# 130731_AriloRX_0_1.net
KiCad netlist of a schematic drawn in EAGLE
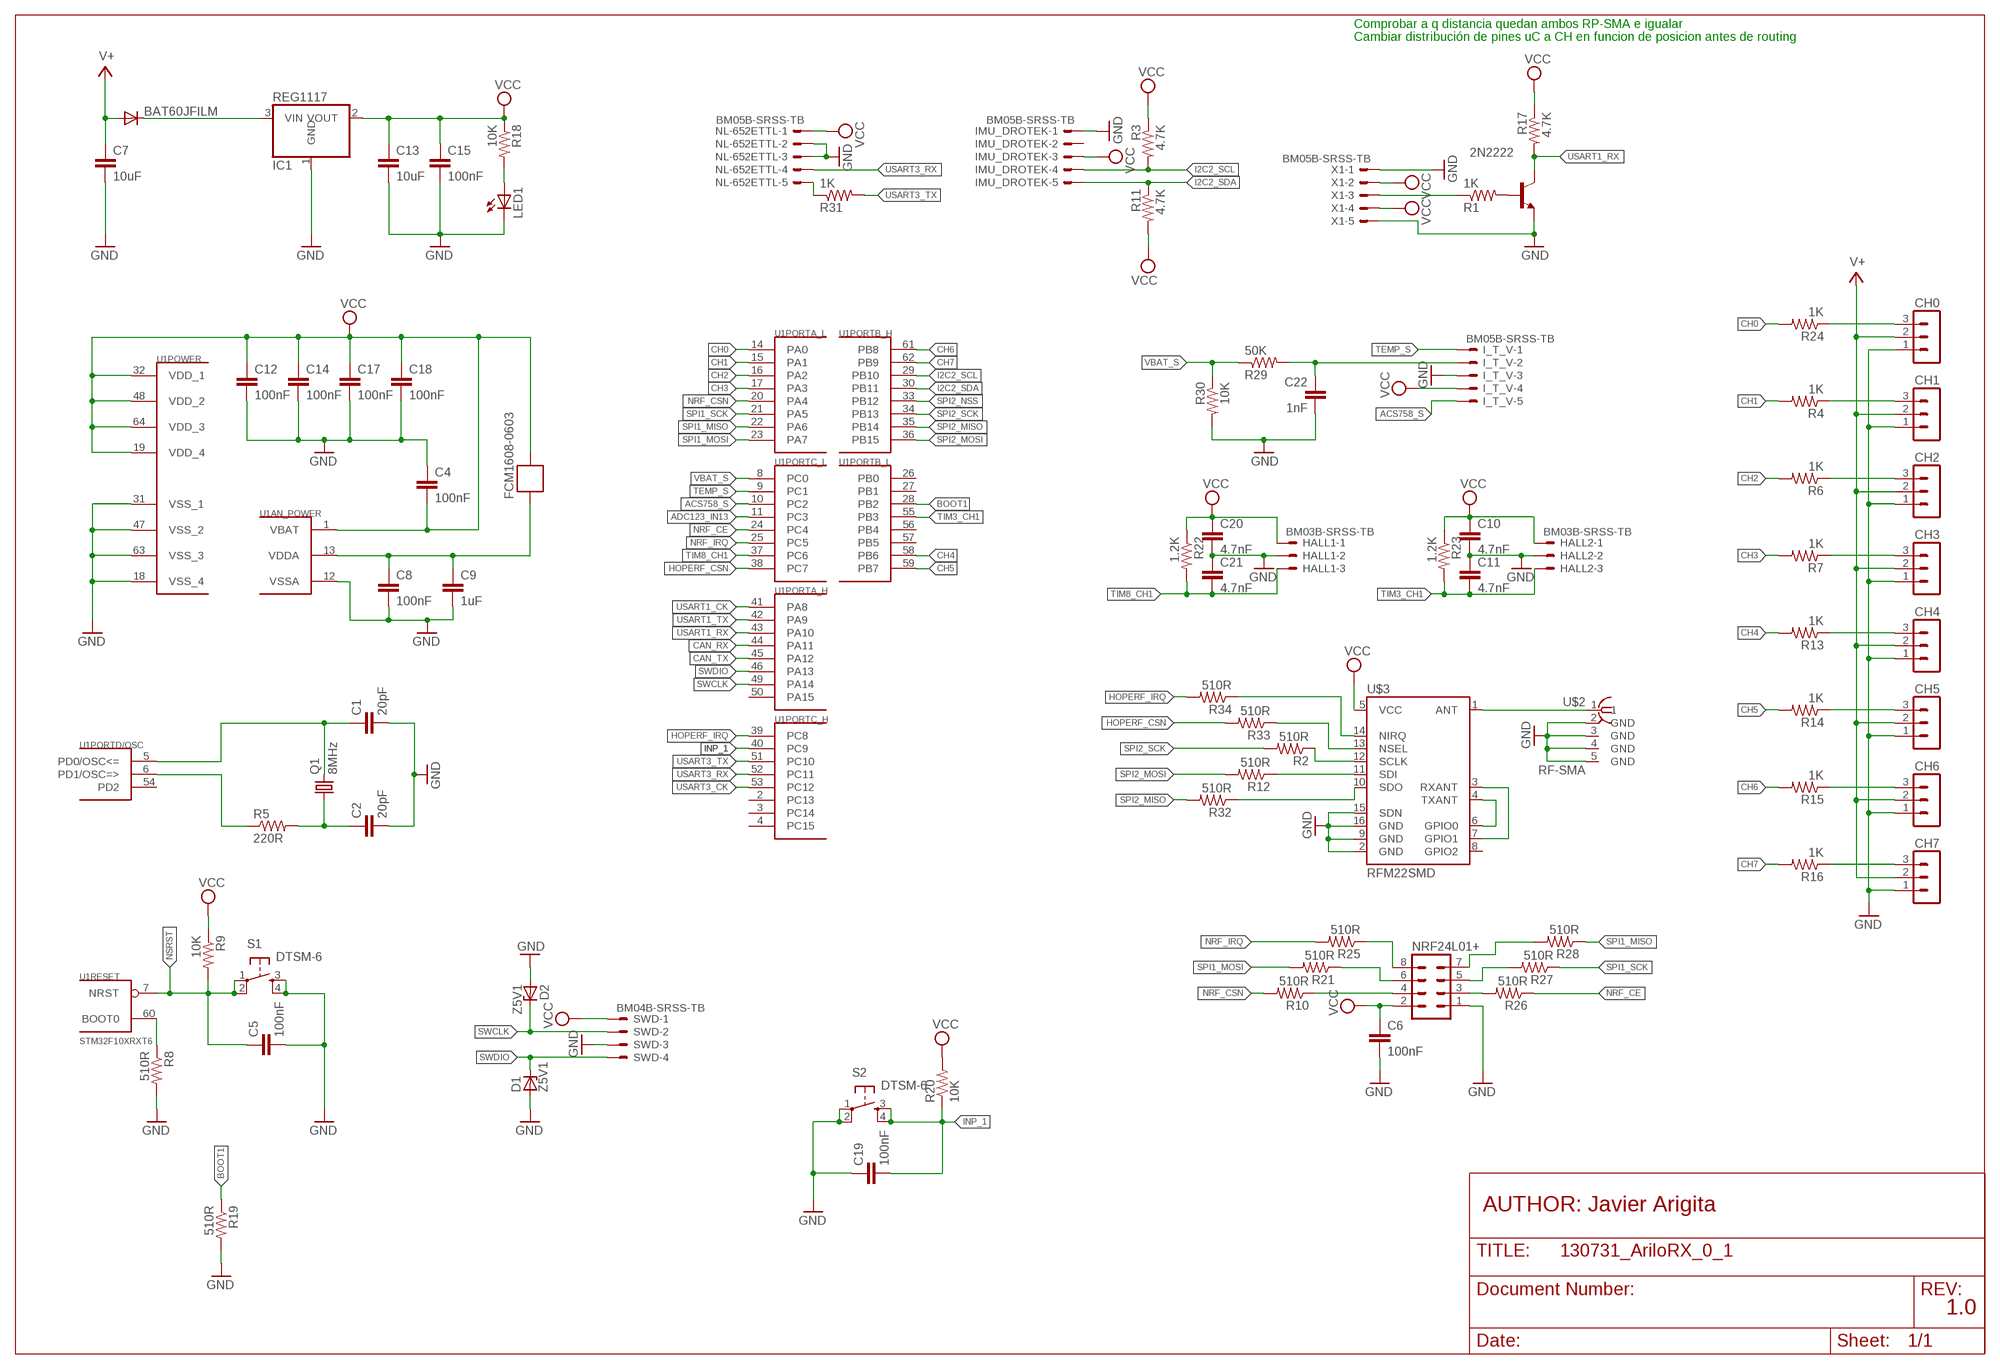
[diagram p0: schematic, sheet 1]

(export (version "E")
  (design (tool "Eeschema 10.0.6"))
  (components
    (comp (ref "2N2222")
      (value "MMBT2222ALT1-NPN-SOT23-BEC")
      (footprint "eagle-import:SOT23-BEC")
      (libsource (lib "eagle-import") (part "-NPN-SOT23-BECMMBT2222ALT1"))
    )
    (comp (ref "BAT60JFILM")
      (value "DIODE-SOD323-R")
      (footprint "eagle-import:SOD323-R")
      (libsource (lib "eagle-import") (part "DIODE-SOD323-R"))
    )
    (comp (ref "C1")
      (value "20pF")
      (footprint "eagle-import:C0805")
      (libsource (lib "eagle-import") (part "C-EUC0805"))
    )
    (comp (ref "C2")
      (value "20pF")
      (footprint "eagle-import:C0805")
      (libsource (lib "eagle-import") (part "C-EUC0805"))
    )
    (comp (ref "C4")
      (value "100nF")
      (footprint "eagle-import:C0805")
      (libsource (lib "eagle-import") (part "C-EUC0805"))
    )
    (comp (ref "C5")
      (value "100nF")
      (footprint "eagle-import:C0805")
      (libsource (lib "eagle-import") (part "C-EUC0805"))
    )
    (comp (ref "C6")
      (value "100nF")
      (footprint "eagle-import:C0805")
      (libsource (lib "eagle-import") (part "C-EUC0805"))
    )
    (comp (ref "C7")
      (value "10uF")
      (footprint "eagle-import:C3216")
      (libsource (lib "eagle-import") (part "resistor_C-EUC3216"))
    )
    (comp (ref "C8")
      (value "100nF")
      (footprint "eagle-import:C0805")
      (libsource (lib "eagle-import") (part "C-EUC0805"))
    )
    (comp (ref "C9")
      (value "1uF")
      (footprint "eagle-import:C3216")
      (libsource (lib "eagle-import") (part "resistor_C-EUC3216"))
    )
    (comp (ref "C10")
      (value "4.7nF")
      (footprint "eagle-import:C0805")
      (libsource (lib "eagle-import") (part "C-EUC0805"))
    )
    (comp (ref "C11")
      (value "4.7nF")
      (footprint "eagle-import:C0805")
      (libsource (lib "eagle-import") (part "C-EUC0805"))
    )
    (comp (ref "C12")
      (value "100nF")
      (footprint "eagle-import:C0805")
      (libsource (lib "eagle-import") (part "C-EUC0805"))
    )
    (comp (ref "C13")
      (value "10uF")
      (footprint "eagle-import:C3216")
      (libsource (lib "eagle-import") (part "resistor_C-EUC3216"))
    )
    (comp (ref "C14")
      (value "100nF")
      (footprint "eagle-import:C0805")
      (libsource (lib "eagle-import") (part "C-EUC0805"))
    )
    (comp (ref "C15")
      (value "100nF")
      (footprint "eagle-import:C0805")
      (libsource (lib "eagle-import") (part "C-EUC0805"))
    )
    (comp (ref "C17")
      (value "100nF")
      (footprint "eagle-import:C0805")
      (libsource (lib "eagle-import") (part "C-EUC0805"))
    )
    (comp (ref "C18")
      (value "100nF")
      (footprint "eagle-import:C0805")
      (libsource (lib "eagle-import") (part "C-EUC0805"))
    )
    (comp (ref "C19")
      (value "100nF")
      (footprint "eagle-import:C0805")
      (libsource (lib "eagle-import") (part "C-EUC0805"))
    )
    (comp (ref "C20")
      (value "4.7nF")
      (footprint "eagle-import:C0805")
      (libsource (lib "eagle-import") (part "C-EUC0805"))
    )
    (comp (ref "C21")
      (value "4.7nF")
      (footprint "eagle-import:C0805")
      (libsource (lib "eagle-import") (part "C-EUC0805"))
    )
    (comp (ref "C22")
      (value "1nF")
      (footprint "eagle-import:C0805")
      (libsource (lib "eagle-import") (part "C-EUC0805"))
    )
    (comp (ref "CH0")
      (value "MA03-1")
      (footprint "eagle-import:MA03-1")
      (libsource (lib "eagle-import") (part "MA03-1"))
    )
    (comp (ref "CH1")
      (value "MA03-1")
      (footprint "eagle-import:MA03-1")
      (libsource (lib "eagle-import") (part "MA03-1"))
    )
    (comp (ref "CH2")
      (value "MA03-1")
      (footprint "eagle-import:MA03-1")
      (libsource (lib "eagle-import") (part "MA03-1"))
    )
    (comp (ref "CH3")
      (value "MA03-1")
      (footprint "eagle-import:MA03-1")
      (libsource (lib "eagle-import") (part "MA03-1"))
    )
    (comp (ref "CH4")
      (value "MA03-1")
      (footprint "eagle-import:MA03-1")
      (libsource (lib "eagle-import") (part "MA03-1"))
    )
    (comp (ref "CH5")
      (value "MA03-1")
      (footprint "eagle-import:MA03-1")
      (libsource (lib "eagle-import") (part "MA03-1"))
    )
    (comp (ref "CH6")
      (value "MA03-1")
      (footprint "eagle-import:MA03-1")
      (libsource (lib "eagle-import") (part "MA03-1"))
    )
    (comp (ref "CH7")
      (value "MA03-1")
      (footprint "eagle-import:MA03-1")
      (libsource (lib "eagle-import") (part "MA03-1"))
    )
    (comp (ref "D1")
      (value "Z5V1")
      (footprint "eagle-import:SOD80C")
      (libsource (lib "eagle-import") (part "ZENER-DIODESOD80C"))
    )
    (comp (ref "D2")
      (value "Z5V1")
      (footprint "eagle-import:SOD80C")
      (libsource (lib "eagle-import") (part "ZENER-DIODESOD80C"))
    )
    (comp (ref "FCM1608-0603")
      (value "FERRITE-BEAD")
      (footprint "eagle-import:R0603")
      (libsource (lib "eagle-import") (part "FERRITE-BEAD"))
    )
    (comp (ref "HALL1")
      (value "BM03B-SRSS-TB")
      (footprint "eagle-import:BM03B-SRSS-TB")
      (libsource (lib "eagle-import") (part "?M03B-SRSS-TBB"))
    )
    (comp (ref "HALL2")
      (value "BM03B-SRSS-TB")
      (footprint "eagle-import:BM03B-SRSS-TB")
      (libsource (lib "eagle-import") (part "?M03B-SRSS-TBB"))
    )
    (comp (ref "IC1")
      (value "REG1117")
      (footprint "eagle-import:SOT223")
      (libsource (lib "eagle-import") (part "REG1117"))
    )
    (comp (ref "IMU_DROTEK")
      (value "BM05B-SRSS-TB")
      (footprint "eagle-import:BM05B-SRSS-TB")
      (libsource (lib "eagle-import") (part "?M05B-SRSS-TBB"))
    )
    (comp (ref "I_T_V")
      (value "BM05B-SRSS-TB")
      (footprint "eagle-import:BM05B-SRSS-TB")
      (libsource (lib "eagle-import") (part "?M05B-SRSS-TBB"))
    )
    (comp (ref "LED1")
      (value "LED0805")
      (footprint "eagle-import:CHIPLED_0805")
      (libsource (lib "eagle-import") (part "LED0805"))
    )
    (comp (ref "NL-652ETTL")
      (value "BM05B-SRSS-TB")
      (footprint "eagle-import:BM05B-SRSS-TB")
      (libsource (lib "eagle-import") (part "?M05B-SRSS-TBB"))
    )
    (comp (ref "NRF24L01+")
      (value "MA04-2")
      (footprint "eagle-import:MA04-2")
      (libsource (lib "eagle-import") (part "MA04-2"))
    )
    (comp (ref "Q1")
      (value "8MHz")
      (footprint "eagle-import:SM49")
      (libsource (lib "eagle-import") (part "CRYSTALSM49"))
    )
    (comp (ref "R1")
      (value "1K")
      (footprint "eagle-import:R0805")
      (libsource (lib "eagle-import") (part "RESISTOR0805"))
    )
    (comp (ref "R2")
      (value "510R")
      (footprint "eagle-import:R0805")
      (libsource (lib "eagle-import") (part "RESISTOR0805"))
    )
    (comp (ref "R3")
      (value "4.7K")
      (footprint "eagle-import:R0805")
      (libsource (lib "eagle-import") (part "RESISTOR0805"))
    )
    (comp (ref "R4")
      (value "1K")
      (footprint "eagle-import:R0805")
      (libsource (lib "eagle-import") (part "RESISTOR0805"))
    )
    (comp (ref "R5")
      (value "220R")
      (footprint "eagle-import:R0805")
      (libsource (lib "eagle-import") (part "RESISTOR0805"))
    )
    (comp (ref "R6")
      (value "1K")
      (footprint "eagle-import:R0805")
      (libsource (lib "eagle-import") (part "RESISTOR0805"))
    )
    (comp (ref "R7")
      (value "1K")
      (footprint "eagle-import:R0805")
      (libsource (lib "eagle-import") (part "RESISTOR0805"))
    )
    (comp (ref "R8")
      (value "510R")
      (footprint "eagle-import:R0805")
      (libsource (lib "eagle-import") (part "RESISTOR0805"))
    )
    (comp (ref "R9")
      (value "10K")
      (footprint "eagle-import:R0805")
      (libsource (lib "eagle-import") (part "RESISTOR0805"))
    )
    (comp (ref "R10")
      (value "510R")
      (footprint "eagle-import:R0805")
      (libsource (lib "eagle-import") (part "RESISTOR0805"))
    )
    (comp (ref "R11")
      (value "4.7K")
      (footprint "eagle-import:R0805")
      (libsource (lib "eagle-import") (part "RESISTOR0805"))
    )
    (comp (ref "R12")
      (value "510R")
      (footprint "eagle-import:R0805")
      (libsource (lib "eagle-import") (part "RESISTOR0805"))
    )
    (comp (ref "R13")
      (value "1K")
      (footprint "eagle-import:R0805")
      (libsource (lib "eagle-import") (part "RESISTOR0805"))
    )
    (comp (ref "R14")
      (value "1K")
      (footprint "eagle-import:R0805")
      (libsource (lib "eagle-import") (part "RESISTOR0805"))
    )
    (comp (ref "R15")
      (value "1K")
      (footprint "eagle-import:R0805")
      (libsource (lib "eagle-import") (part "RESISTOR0805"))
    )
    (comp (ref "R16")
      (value "1K")
      (footprint "eagle-import:R0805")
      (libsource (lib "eagle-import") (part "RESISTOR0805"))
    )
    (comp (ref "R17")
      (value "4.7K")
      (footprint "eagle-import:R0805")
      (libsource (lib "eagle-import") (part "RESISTOR0805"))
    )
    (comp (ref "R18")
      (value "10K")
      (footprint "eagle-import:R0805")
      (libsource (lib "eagle-import") (part "RESISTOR0805"))
    )
    (comp (ref "R19")
      (value "510R")
      (footprint "eagle-import:R0805")
      (libsource (lib "eagle-import") (part "RESISTOR0805"))
    )
    (comp (ref "R20")
      (value "10K")
      (footprint "eagle-import:R0805")
      (libsource (lib "eagle-import") (part "RESISTOR0805"))
    )
    (comp (ref "R21")
      (value "510R")
      (footprint "eagle-import:R0805")
      (libsource (lib "eagle-import") (part "RESISTOR0805"))
    )
    (comp (ref "R22")
      (value "1.2K")
      (footprint "eagle-import:R0805")
      (libsource (lib "eagle-import") (part "RESISTOR0805"))
    )
    (comp (ref "R23")
      (value "1.2K")
      (footprint "eagle-import:R0805")
      (libsource (lib "eagle-import") (part "RESISTOR0805"))
    )
    (comp (ref "R24")
      (value "1K")
      (footprint "eagle-import:R0805")
      (libsource (lib "eagle-import") (part "RESISTOR0805"))
    )
    (comp (ref "R25")
      (value "510R")
      (footprint "eagle-import:R0805")
      (libsource (lib "eagle-import") (part "RESISTOR0805"))
    )
    (comp (ref "R26")
      (value "510R")
      (footprint "eagle-import:R0805")
      (libsource (lib "eagle-import") (part "RESISTOR0805"))
    )
    (comp (ref "R27")
      (value "510R")
      (footprint "eagle-import:R0805")
      (libsource (lib "eagle-import") (part "RESISTOR0805"))
    )
    (comp (ref "R28")
      (value "510R")
      (footprint "eagle-import:R0805")
      (libsource (lib "eagle-import") (part "RESISTOR0805"))
    )
    (comp (ref "R29")
      (value "50K")
      (footprint "eagle-import:R0805")
      (libsource (lib "eagle-import") (part "RESISTOR0805"))
    )
    (comp (ref "R30")
      (value "10K")
      (footprint "eagle-import:R0805")
      (libsource (lib "eagle-import") (part "RESISTOR0805"))
    )
    (comp (ref "R31")
      (value "1K")
      (footprint "eagle-import:R0805")
      (libsource (lib "eagle-import") (part "RESISTOR0805"))
    )
    (comp (ref "R32")
      (value "510R")
      (footprint "eagle-import:R0805")
      (libsource (lib "eagle-import") (part "RESISTOR0805"))
    )
    (comp (ref "R33")
      (value "510R")
      (footprint "eagle-import:R0805")
      (libsource (lib "eagle-import") (part "RESISTOR0805"))
    )
    (comp (ref "R34")
      (value "510R")
      (footprint "eagle-import:R0805")
      (libsource (lib "eagle-import") (part "RESISTOR0805"))
    )
    (comp (ref "S1")
      (value "DTSM-6")
      (footprint "eagle-import:DTSM-6")
      (libsource (lib "eagle-import") (part "DTSM-6"))
    )
    (comp (ref "S2")
      (value "DTSM-6")
      (footprint "eagle-import:DTSM-6")
      (libsource (lib "eagle-import") (part "DTSM-6"))
    )
    (comp (ref "SWD")
      (value "BM04B-SRSS-TB")
      (footprint "eagle-import:BM04B-SRSS-TB")
      (libsource (lib "eagle-import") (part "?M04B-SRSS-TBB"))
    )
    (comp (ref "U$2")
      (value "RF-SMA")
      (footprint "eagle-import:BU-SMA-H")
      (libsource (lib "eagle-import") (part "RF-SMA"))
    )
    (comp (ref "U$3")
      (value "RFM22SMD")
      (footprint "eagle-import:RFM22-XXX-S2")
      (libsource (lib "eagle-import") (part "RFM22SMD"))
    )
    (comp (ref "U1")
      (value "STM32F10XRXT6")
      (footprint "eagle-import:TQFP64")
      (libsource (lib "eagle-import") (part "STM32F10XRXT6"))
    )
    (comp (ref "X1")
      (value "BM05B-SRSS-TB")
      (footprint "eagle-import:BM05B-SRSS-TB")
      (libsource (lib "eagle-import") (part "?M05B-SRSS-TBB"))
    )
  )
  (nets
    (net (code "1") (name "ACS758_S") (class "Default")
      (node (ref "I_T_V") (pin "5") (pinfunction "S_5") (pintype "passive"))
      (node (ref "U1") (pin "10") (pinfunction "PC2_10") (pintype "bidirectional"))
    )
    (net (code "2") (name "ADC123_IN13") (class "Default")
      (node (ref "U1") (pin "11") (pinfunction "PC3_11") (pintype "bidirectional"))
    )
    (net (code "3") (name "BOOT1") (class "Default")
      (node (ref "R19") (pin "1") (pinfunction "1_1") (pintype "passive"))
      (node (ref "U1") (pin "28") (pinfunction "PB2_28") (pintype "bidirectional"))
    )
    (net (code "4") (name "CAN_RX") (class "Default")
      (node (ref "U1") (pin "44") (pinfunction "PA11_44") (pintype "bidirectional"))
    )
    (net (code "5") (name "CAN_TX") (class "Default")
      (node (ref "U1") (pin "45") (pinfunction "PA12_45") (pintype "bidirectional"))
    )
    (net (code "6") (name "CH0") (class "Default")
      (node (ref "R24") (pin "2") (pinfunction "2_2") (pintype "passive"))
      (node (ref "U1") (pin "14") (pinfunction "PA0_14") (pintype "bidirectional"))
    )
    (net (code "7") (name "CH1") (class "Default")
      (node (ref "R4") (pin "2") (pinfunction "2_2") (pintype "passive"))
      (node (ref "U1") (pin "15") (pinfunction "PA1_15") (pintype "bidirectional"))
    )
    (net (code "8") (name "CH2") (class "Default")
      (node (ref "R6") (pin "2") (pinfunction "2_2") (pintype "passive"))
      (node (ref "U1") (pin "16") (pinfunction "PA2_16") (pintype "bidirectional"))
    )
    (net (code "9") (name "CH3") (class "Default")
      (node (ref "R7") (pin "2") (pinfunction "2_2") (pintype "passive"))
      (node (ref "U1") (pin "17") (pinfunction "PA3_17") (pintype "bidirectional"))
    )
    (net (code "10") (name "CH4") (class "Default")
      (node (ref "R13") (pin "2") (pinfunction "2_2") (pintype "passive"))
      (node (ref "U1") (pin "58") (pinfunction "PB6_58") (pintype "bidirectional"))
    )
    (net (code "11") (name "CH5") (class "Default")
      (node (ref "R14") (pin "2") (pinfunction "2_2") (pintype "passive"))
      (node (ref "U1") (pin "59") (pinfunction "PB7_59") (pintype "bidirectional"))
    )
    (net (code "12") (name "CH6") (class "Default")
      (node (ref "R15") (pin "2") (pinfunction "2_2") (pintype "passive"))
      (node (ref "U1") (pin "61") (pinfunction "PB8_61") (pintype "bidirectional"))
    )
    (net (code "13") (name "CH7") (class "Default")
      (node (ref "R16") (pin "2") (pinfunction "2_2") (pintype "passive"))
      (node (ref "U1") (pin "62") (pinfunction "PB9_62") (pintype "bidirectional"))
    )
    (net (code "14") (name "GND") (class "Default")
      (node (ref "2N2222") (pin "E") (pinfunction "E_E") (pintype "passive"))
      (node (ref "C1") (pin "2") (pinfunction "2_2") (pintype "passive"))
      (node (ref "C10") (pin "2") (pinfunction "2_2") (pintype "passive"))
      (node (ref "C11") (pin "1") (pinfunction "1_1") (pintype "passive"))
      (node (ref "C12") (pin "2") (pinfunction "2_2") (pintype "passive"))
      (node (ref "C13") (pin "2") (pinfunction "2_2") (pintype "passive"))
      (node (ref "C14") (pin "2") (pinfunction "2_2") (pintype "passive"))
      (node (ref "C15") (pin "2") (pinfunction "2_2") (pintype "passive"))
      (node (ref "C17") (pin "2") (pinfunction "2_2") (pintype "passive"))
      (node (ref "C18") (pin "2") (pinfunction "2_2") (pintype "passive"))
      (node (ref "C19") (pin "1") (pinfunction "1_1") (pintype "passive"))
      (node (ref "C2") (pin "2") (pinfunction "2_2") (pintype "passive"))
      (node (ref "C20") (pin "2") (pinfunction "2_2") (pintype "passive"))
      (node (ref "C21") (pin "1") (pinfunction "1_1") (pintype "passive"))
      (node (ref "C22") (pin "2") (pinfunction "2_2") (pintype "passive"))
      (node (ref "C4") (pin "1") (pinfunction "1_1") (pintype "passive"))
      (node (ref "C5") (pin "2") (pinfunction "2_2") (pintype "passive"))
      (node (ref "C6") (pin "2") (pinfunction "2_2") (pintype "passive"))
      (node (ref "C7") (pin "2") (pinfunction "2_2") (pintype "passive"))
      (node (ref "C8") (pin "2") (pinfunction "2_2") (pintype "passive"))
      (node (ref "C9") (pin "2") (pinfunction "2_2") (pintype "passive"))
      (node (ref "CH0") (pin "1") (pinfunction "1_1") (pintype "passive"))
      (node (ref "CH1") (pin "1") (pinfunction "1_1") (pintype "passive"))
      (node (ref "CH2") (pin "1") (pinfunction "1_1") (pintype "passive"))
      (node (ref "CH3") (pin "1") (pinfunction "1_1") (pintype "passive"))
      (node (ref "CH4") (pin "1") (pinfunction "1_1") (pintype "passive"))
      (node (ref "CH5") (pin "1") (pinfunction "1_1") (pintype "passive"))
      (node (ref "CH6") (pin "1") (pinfunction "1_1") (pintype "passive"))
      (node (ref "CH7") (pin "1") (pinfunction "1_1") (pintype "passive"))
      (node (ref "D1") (pin "A") (pinfunction "A_A") (pintype "passive"))
      (node (ref "D2") (pin "A") (pinfunction "A_A") (pintype "passive"))
      (node (ref "HALL1") (pin "2") (pinfunction "S_2") (pintype "passive"))
      (node (ref "HALL2") (pin "2") (pinfunction "S_2") (pintype "passive"))
      (node (ref "IC1") (pin "1") (pinfunction "GND_1") (pintype "power_in"))
      (node (ref "IMU_DROTEK") (pin "1") (pinfunction "S_1") (pintype "passive"))
      (node (ref "I_T_V") (pin "3") (pinfunction "S_3") (pintype "passive"))
      (node (ref "LED1") (pin "C") (pinfunction "C_C") (pintype "passive"))
      (node (ref "NL-652ETTL") (pin "2") (pinfunction "S_2") (pintype "passive"))
      (node (ref "NL-652ETTL") (pin "3") (pinfunction "S_3") (pintype "passive"))
      (node (ref "NRF24L01+") (pin "1") (pinfunction "1_1") (pintype "passive"))
      (node (ref "R19") (pin "2") (pinfunction "2_2") (pintype "passive"))
      (node (ref "R30") (pin "2") (pinfunction "2_2") (pintype "passive"))
      (node (ref "R8") (pin "2") (pinfunction "2_2") (pintype "passive"))
      (node (ref "S1") (pin "3") (pinfunction "3_3") (pintype "passive"))
      (node (ref "S1") (pin "4") (pinfunction "4_4") (pintype "passive"))
      (node (ref "S2") (pin "1") (pinfunction "1_1") (pintype "passive"))
      (node (ref "S2") (pin "2") (pinfunction "2_2") (pintype "passive"))
      (node (ref "SWD") (pin "3") (pinfunction "S_3") (pintype "passive"))
      (node (ref "U$2") (pin "2") (pinfunction "GND_2") (pintype "power_in"))
      (node (ref "U$2") (pin "3") (pinfunction "GND_3") (pintype "bidirectional"))
      (node (ref "U$2") (pin "4") (pinfunction "GND_4") (pintype "bidirectional"))
      (node (ref "U$2") (pin "5") (pinfunction "GND_5") (pintype "bidirectional"))
      (node (ref "U$3") (pin "15") (pinfunction "SDN_15") (pintype "input"))
      (node (ref "U$3") (pin "16") (pinfunction "GND_16") (pintype "power_in"))
      (node (ref "U$3") (pin "2") (pinfunction "GND_2") (pintype "power_in"))
      (node (ref "U$3") (pin "9") (pinfunction "GND_9") (pintype "power_in"))
      (node (ref "U1") (pin "12") (pinfunction "VSSA_12") (pintype "power_in"))
      (node (ref "U1") (pin "18") (pinfunction "VSS_4_18") (pintype "power_in"))
      (node (ref "U1") (pin "31") (pinfunction "VSS_1_31") (pintype "power_in"))
      (node (ref "U1") (pin "47") (pinfunction "VSS_2_47") (pintype "power_in"))
      (node (ref "U1") (pin "63") (pinfunction "VSS_3_63") (pintype "power_in"))
      (node (ref "X1") (pin "1") (pinfunction "S_1") (pintype "passive"))
      (node (ref "X1") (pin "5") (pinfunction "S_5") (pintype "passive"))
    )
    (net (code "15") (name "HOPERF_CSN") (class "Default")
      (node (ref "R33") (pin "2") (pinfunction "2_2") (pintype "passive"))
      (node (ref "U1") (pin "38") (pinfunction "PC7_38") (pintype "bidirectional"))
    )
    (net (code "16") (name "HOPERF_IRQ") (class "Default")
      (node (ref "R34") (pin "2") (pinfunction "2_2") (pintype "passive"))
      (node (ref "U1") (pin "39") (pinfunction "PC8_39") (pintype "bidirectional"))
    )
    (net (code "17") (name "I2C2_SCL") (class "Default")
      (node (ref "IMU_DROTEK") (pin "4") (pinfunction "S_4") (pintype "passive"))
      (node (ref "R3") (pin "2") (pinfunction "2_2") (pintype "passive"))
      (node (ref "U1") (pin "29") (pinfunction "PB10_29") (pintype "bidirectional"))
    )
    (net (code "18") (name "I2C2_SDA") (class "Default")
      (node (ref "IMU_DROTEK") (pin "5") (pinfunction "S_5") (pintype "passive"))
      (node (ref "R11") (pin "1") (pinfunction "1_1") (pintype "passive"))
      (node (ref "U1") (pin "30") (pinfunction "PB11_30") (pintype "bidirectional"))
    )
    (net (code "19") (name "INP_1") (class "Default")
      (node (ref "C19") (pin "2") (pinfunction "2_2") (pintype "passive"))
      (node (ref "R20") (pin "1") (pinfunction "1_1") (pintype "passive"))
      (node (ref "S2") (pin "3") (pinfunction "3_3") (pintype "passive"))
      (node (ref "S2") (pin "4") (pinfunction "4_4") (pintype "passive"))
      (node (ref "U1") (pin "40") (pinfunction "PC9_40") (pintype "bidirectional"))
    )
    (net (code "20") (name "NRF_CE") (class "Default")
      (node (ref "R26") (pin "1") (pinfunction "1_1") (pintype "passive"))
      (node (ref "U1") (pin "24") (pinfunction "PC4_24") (pintype "bidirectional"))
    )
    (net (code "21") (name "NRF_CSN") (class "Default")
      (node (ref "R10") (pin "2") (pinfunction "2_2") (pintype "passive"))
      (node (ref "U1") (pin "20") (pinfunction "PA4_20") (pintype "bidirectional"))
    )
    (net (code "22") (name "NRF_IRQ") (class "Default")
      (node (ref "R25") (pin "2") (pinfunction "2_2") (pintype "passive"))
      (node (ref "U1") (pin "25") (pinfunction "PC5_25") (pintype "bidirectional"))
    )
    (net (code "23") (name "NSRST") (class "Default")
      (node (ref "C5") (pin "1") (pinfunction "1_1") (pintype "passive"))
      (node (ref "R9") (pin "2") (pinfunction "2_2") (pintype "passive"))
      (node (ref "S1") (pin "1") (pinfunction "1_1") (pintype "passive"))
      (node (ref "S1") (pin "2") (pinfunction "2_2") (pintype "passive"))
      (node (ref "U1") (pin "7") (pinfunction "NRST_7") (pintype "input"))
    )
    (net (code "24") (name "Net-(2N2222-PadB)") (class "Default")
      (node (ref "2N2222") (pin "B") (pinfunction "B_B") (pintype "passive"))
      (node (ref "R1") (pin "2") (pinfunction "2_2") (pintype "passive"))
    )
    (net (code "25") (name "Net-(C2-Pad1)") (class "Default")
      (node (ref "C2") (pin "1") (pinfunction "1_1") (pintype "passive"))
      (node (ref "Q1") (pin "1") (pinfunction "1_1") (pintype "passive"))
      (node (ref "R5") (pin "2") (pinfunction "2_2") (pintype "passive"))
    )
    (net (code "26") (name "Net-(CH0-Pad3)") (class "Default")
      (node (ref "CH0") (pin "3") (pinfunction "3_3") (pintype "passive"))
      (node (ref "R24") (pin "1") (pinfunction "1_1") (pintype "passive"))
    )
    (net (code "27") (name "Net-(CH1-Pad3)") (class "Default")
      (node (ref "CH1") (pin "3") (pinfunction "3_3") (pintype "passive"))
      (node (ref "R4") (pin "1") (pinfunction "1_1") (pintype "passive"))
    )
    (net (code "28") (name "Net-(CH2-Pad3)") (class "Default")
      (node (ref "CH2") (pin "3") (pinfunction "3_3") (pintype "passive"))
      (node (ref "R6") (pin "1") (pinfunction "1_1") (pintype "passive"))
    )
    (net (code "29") (name "Net-(CH3-Pad3)") (class "Default")
      (node (ref "CH3") (pin "3") (pinfunction "3_3") (pintype "passive"))
      (node (ref "R7") (pin "1") (pinfunction "1_1") (pintype "passive"))
    )
    (net (code "30") (name "Net-(CH4-Pad3)") (class "Default")
      (node (ref "CH4") (pin "3") (pinfunction "3_3") (pintype "passive"))
      (node (ref "R13") (pin "1") (pinfunction "1_1") (pintype "passive"))
    )
    (net (code "31") (name "Net-(CH5-Pad3)") (class "Default")
      (node (ref "CH5") (pin "3") (pinfunction "3_3") (pintype "passive"))
      (node (ref "R14") (pin "1") (pinfunction "1_1") (pintype "passive"))
    )
    (net (code "32") (name "Net-(CH6-Pad3)") (class "Default")
      (node (ref "CH6") (pin "3") (pinfunction "3_3") (pintype "passive"))
      (node (ref "R15") (pin "1") (pinfunction "1_1") (pintype "passive"))
    )
    (net (code "33") (name "Net-(CH7-Pad3)") (class "Default")
      (node (ref "CH7") (pin "3") (pinfunction "3_3") (pintype "passive"))
      (node (ref "R16") (pin "1") (pinfunction "1_1") (pintype "passive"))
    )
    (net (code "34") (name "Net-(FCM1608-0603-P$2)") (class "Default")
      (node (ref "C8") (pin "1") (pinfunction "1_1") (pintype "passive"))
      (node (ref "C9") (pin "1") (pinfunction "1_1") (pintype "passive"))
      (node (ref "FCM1608-0603") (pin "2") (pinfunction "P$2_2") (pintype "bidirectional"))
      (node (ref "U1") (pin "13") (pinfunction "VDDA_13") (pintype "power_in"))
    )
    (net (code "35") (name "Net-(IC1-VIN)") (class "Default")
      (node (ref "BAT60JFILM") (pin "C") (pinfunction "C_C") (pintype "passive"))
      (node (ref "IC1") (pin "3") (pinfunction "VIN_3") (pintype "input"))
    )
    (net (code "36") (name "Net-(I_T_VB-S)") (class "Default")
      (node (ref "C22") (pin "1") (pinfunction "1_1") (pintype "passive"))
      (node (ref "I_T_V") (pin "2") (pinfunction "S_2") (pintype "passive"))
      (node (ref "R29") (pin "2") (pinfunction "2_2") (pintype "passive"))
    )
    (net (code "37") (name "Net-(LED1-PadA)") (class "Default")
      (node (ref "LED1") (pin "A") (pinfunction "A_A") (pintype "passive"))
      (node (ref "R18") (pin "2") (pinfunction "2_2") (pintype "passive"))
    )
    (net (code "38") (name "Net-(NL-652ETTLE-S)") (class "Default")
      (node (ref "NL-652ETTL") (pin "5") (pinfunction "S_5") (pintype "passive"))
      (node (ref "R31") (pin "1") (pinfunction "1_1") (pintype "passive"))
    )
    (net (code "39") (name "Net-(NRF24L01+-Pad3)") (class "Default")
      (node (ref "NRF24L01+") (pin "3") (pinfunction "3_3") (pintype "passive"))
      (node (ref "R26") (pin "2") (pinfunction "2_2") (pintype "passive"))
    )
    (net (code "40") (name "Net-(NRF24L01+-Pad4)") (class "Default")
      (node (ref "NRF24L01+") (pin "4") (pinfunction "4_4") (pintype "passive"))
      (node (ref "R10") (pin "1") (pinfunction "1_1") (pintype "passive"))
    )
    (net (code "41") (name "Net-(NRF24L01+-Pad5)") (class "Default")
      (node (ref "NRF24L01+") (pin "5") (pinfunction "5_5") (pintype "passive"))
      (node (ref "R27") (pin "2") (pinfunction "2_2") (pintype "passive"))
    )
    (net (code "42") (name "Net-(NRF24L01+-Pad6)") (class "Default")
      (node (ref "NRF24L01+") (pin "6") (pinfunction "6_6") (pintype "passive"))
      (node (ref "R21") (pin "1") (pinfunction "1_1") (pintype "passive"))
    )
    (net (code "43") (name "Net-(NRF24L01+-Pad7)") (class "Default")
      (node (ref "NRF24L01+") (pin "7") (pinfunction "7_7") (pintype "passive"))
      (node (ref "R28") (pin "2") (pinfunction "2_2") (pintype "passive"))
    )
    (net (code "44") (name "Net-(NRF24L01+-Pad8)") (class "Default")
      (node (ref "NRF24L01+") (pin "8") (pinfunction "8_8") (pintype "passive"))
      (node (ref "R25") (pin "1") (pinfunction "1_1") (pintype "passive"))
    )
    (net (code "45") (name "Net-(U$3-ANT)") (class "Default")
      (node (ref "U$2") (pin "1") (pinfunction "1_1") (pintype "passive"))
      (node (ref "U$3") (pin "1") (pinfunction "ANT_1") (pintype "bidirectional"))
    )
    (net (code "46") (name "Net-(U$3-GPIO0)") (class "Default")
      (node (ref "U$3") (pin "4") (pinfunction "TXANT_4") (pintype "input"))
      (node (ref "U$3") (pin "6") (pinfunction "GPIO0_6") (pintype "bidirectional"))
    )
    (net (code "47") (name "Net-(U$3-GPIO1)") (class "Default")
      (node (ref "U$3") (pin "3") (pinfunction "RXANT_3") (pintype "input"))
      (node (ref "U$3") (pin "7") (pinfunction "GPIO1_7") (pintype "bidirectional"))
    )
    (net (code "48") (name "Net-(U$3-NIRQ)") (class "Default")
      (node (ref "R34") (pin "1") (pinfunction "1_1") (pintype "passive"))
      (node (ref "U$3") (pin "14") (pinfunction "NIRQ_14") (pintype "output"))
    )
    (net (code "49") (name "Net-(U$3-NSEL)") (class "Default")
      (node (ref "R33") (pin "1") (pinfunction "1_1") (pintype "passive"))
      (node (ref "U$3") (pin "13") (pinfunction "NSEL_13") (pintype "input"))
    )
    (net (code "50") (name "Net-(U$3-SCLK)") (class "Default")
      (node (ref "R2") (pin "1") (pinfunction "1_1") (pintype "passive"))
      (node (ref "U$3") (pin "12") (pinfunction "SCLK_12") (pintype "input"))
    )
    (net (code "51") (name "Net-(U$3-SDI)") (class "Default")
      (node (ref "R12") (pin "1") (pinfunction "1_1") (pintype "passive"))
      (node (ref "U$3") (pin "11") (pinfunction "SDI_11") (pintype "input"))
    )
    (net (code "52") (name "Net-(U$3-SDO)") (class "Default")
      (node (ref "R32") (pin "1") (pinfunction "1_1") (pintype "passive"))
      (node (ref "U$3") (pin "10") (pinfunction "SDO_10") (pintype "output"))
    )
    (net (code "53") (name "Net-(U1H-PD0{slash}OSC<=)") (class "Default")
      (node (ref "C1") (pin "1") (pinfunction "1_1") (pintype "passive"))
      (node (ref "Q1") (pin "2") (pinfunction "2_2") (pintype "passive"))
      (node (ref "U1") (pin "5") (pinfunction "PD0/OSC<=_5") (pintype "bidirectional"))
    )
    (net (code "54") (name "Net-(U1H-PD1{slash}OSC=>)") (class "Default")
      (node (ref "R5") (pin "1") (pinfunction "1_1") (pintype "passive"))
      (node (ref "U1") (pin "6") (pinfunction "PD1/OSC=>_6") (pintype "bidirectional"))
    )
    (net (code "55") (name "Net-(U1J-BOOT0)") (class "Default")
      (node (ref "R8") (pin "1") (pinfunction "1_1") (pintype "passive"))
      (node (ref "U1") (pin "60") (pinfunction "BOOT0_60") (pintype "input"))
    )
    (net (code "56") (name "Net-(X1C-S)") (class "Default")
      (node (ref "R1") (pin "1") (pinfunction "1_1") (pintype "passive"))
      (node (ref "X1") (pin "3") (pinfunction "S_3") (pintype "passive"))
    )
    (net (code "57") (name "SPI1_MISO") (class "Default")
      (node (ref "R28") (pin "1") (pinfunction "1_1") (pintype "passive"))
      (node (ref "U1") (pin "22") (pinfunction "PA6_22") (pintype "bidirectional"))
    )
    (net (code "58") (name "SPI1_MOSI") (class "Default")
      (node (ref "R21") (pin "2") (pinfunction "2_2") (pintype "passive"))
      (node (ref "U1") (pin "23") (pinfunction "PA7_23") (pintype "bidirectional"))
    )
    (net (code "59") (name "SPI1_SCK") (class "Default")
      (node (ref "R27") (pin "1") (pinfunction "1_1") (pintype "passive"))
      (node (ref "U1") (pin "21") (pinfunction "PA5_21") (pintype "bidirectional"))
    )
    (net (code "60") (name "SPI2_MISO") (class "Default")
      (node (ref "R32") (pin "2") (pinfunction "2_2") (pintype "passive"))
      (node (ref "U1") (pin "35") (pinfunction "PB14_35") (pintype "bidirectional"))
    )
    (net (code "61") (name "SPI2_MOSI") (class "Default")
      (node (ref "R12") (pin "2") (pinfunction "2_2") (pintype "passive"))
      (node (ref "U1") (pin "36") (pinfunction "PB15_36") (pintype "bidirectional"))
    )
    (net (code "62") (name "SPI2_NSS") (class "Default")
      (node (ref "U1") (pin "33") (pinfunction "PB12_33") (pintype "bidirectional"))
    )
    (net (code "63") (name "SPI2_SCK") (class "Default")
      (node (ref "R2") (pin "2") (pinfunction "2_2") (pintype "passive"))
      (node (ref "U1") (pin "34") (pinfunction "PB13_34") (pintype "bidirectional"))
    )
    (net (code "64") (name "SWCLK") (class "Default")
      (node (ref "D2") (pin "C") (pinfunction "C_C") (pintype "passive"))
      (node (ref "SWD") (pin "2") (pinfunction "S_2") (pintype "passive"))
      (node (ref "U1") (pin "49") (pinfunction "PA14_49") (pintype "bidirectional"))
    )
    (net (code "65") (name "SWDIO") (class "Default")
      (node (ref "D1") (pin "C") (pinfunction "C_C") (pintype "passive"))
      (node (ref "SWD") (pin "4") (pinfunction "S_4") (pintype "passive"))
      (node (ref "U1") (pin "46") (pinfunction "PA13_46") (pintype "bidirectional"))
    )
    (net (code "66") (name "TEMP_S") (class "Default")
      (node (ref "I_T_V") (pin "1") (pinfunction "S_1") (pintype "passive"))
      (node (ref "U1") (pin "9") (pinfunction "PC1_9") (pintype "bidirectional"))
    )
    (net (code "67") (name "TIM3_CH1") (class "Default")
      (node (ref "C11") (pin "2") (pinfunction "2_2") (pintype "passive"))
      (node (ref "HALL2") (pin "3") (pinfunction "S_3") (pintype "passive"))
      (node (ref "R23") (pin "2") (pinfunction "2_2") (pintype "passive"))
      (node (ref "U1") (pin "55") (pinfunction "PB3_55") (pintype "bidirectional"))
    )
    (net (code "68") (name "TIM8_CH1") (class "Default")
      (node (ref "C21") (pin "2") (pinfunction "2_2") (pintype "passive"))
      (node (ref "HALL1") (pin "3") (pinfunction "S_3") (pintype "passive"))
      (node (ref "R22") (pin "2") (pinfunction "2_2") (pintype "passive"))
      (node (ref "U1") (pin "37") (pinfunction "PC6_37") (pintype "bidirectional"))
    )
    (net (code "69") (name "USART1_CK") (class "Default")
      (node (ref "U1") (pin "41") (pinfunction "PA8_41") (pintype "bidirectional"))
    )
    (net (code "70") (name "USART1_RX") (class "Default")
      (node (ref "2N2222") (pin "C") (pinfunction "C_C") (pintype "passive"))
      (node (ref "R17") (pin "2") (pinfunction "2_2") (pintype "passive"))
      (node (ref "U1") (pin "43") (pinfunction "PA10_43") (pintype "bidirectional"))
    )
    (net (code "71") (name "USART1_TX") (class "Default")
      (node (ref "U1") (pin "42") (pinfunction "PA9_42") (pintype "bidirectional"))
    )
    (net (code "72") (name "USART3_CK") (class "Default")
      (node (ref "U1") (pin "53") (pinfunction "PC12_53") (pintype "bidirectional"))
    )
    (net (code "73") (name "USART3_RX") (class "Default")
      (node (ref "NL-652ETTL") (pin "4") (pinfunction "S_4") (pintype "passive"))
      (node (ref "U1") (pin "52") (pinfunction "PC11_52") (pintype "bidirectional"))
    )
    (net (code "74") (name "USART3_TX") (class "Default")
      (node (ref "R31") (pin "2") (pinfunction "2_2") (pintype "passive"))
      (node (ref "U1") (pin "51") (pinfunction "PC10_51") (pintype "bidirectional"))
    )
    (net (code "75") (name "V+") (class "Default")
      (node (ref "BAT60JFILM") (pin "A") (pinfunction "A_A") (pintype "passive"))
      (node (ref "C7") (pin "1") (pinfunction "1_1") (pintype "passive"))
      (node (ref "CH0") (pin "2") (pinfunction "2_2") (pintype "passive"))
      (node (ref "CH1") (pin "2") (pinfunction "2_2") (pintype "passive"))
      (node (ref "CH2") (pin "2") (pinfunction "2_2") (pintype "passive"))
      (node (ref "CH3") (pin "2") (pinfunction "2_2") (pintype "passive"))
      (node (ref "CH4") (pin "2") (pinfunction "2_2") (pintype "passive"))
      (node (ref "CH5") (pin "2") (pinfunction "2_2") (pintype "passive"))
      (node (ref "CH6") (pin "2") (pinfunction "2_2") (pintype "passive"))
      (node (ref "CH7") (pin "2") (pinfunction "2_2") (pintype "passive"))
    )
    (net (code "76") (name "VBAT_S") (class "Default")
      (node (ref "R29") (pin "1") (pinfunction "1_1") (pintype "passive"))
      (node (ref "R30") (pin "1") (pinfunction "1_1") (pintype "passive"))
      (node (ref "U1") (pin "8") (pinfunction "PC0_8") (pintype "bidirectional"))
    )
    (net (code "77") (name "VCC") (class "Default")
      (node (ref "C10") (pin "1") (pinfunction "1_1") (pintype "passive"))
      (node (ref "C12") (pin "1") (pinfunction "1_1") (pintype "passive"))
      (node (ref "C13") (pin "1") (pinfunction "1_1") (pintype "passive"))
      (node (ref "C14") (pin "1") (pinfunction "1_1") (pintype "passive"))
      (node (ref "C15") (pin "1") (pinfunction "1_1") (pintype "passive"))
      (node (ref "C17") (pin "1") (pinfunction "1_1") (pintype "passive"))
      (node (ref "C18") (pin "1") (pinfunction "1_1") (pintype "passive"))
      (node (ref "C20") (pin "1") (pinfunction "1_1") (pintype "passive"))
      (node (ref "C4") (pin "2") (pinfunction "2_2") (pintype "passive"))
      (node (ref "C6") (pin "1") (pinfunction "1_1") (pintype "passive"))
      (node (ref "FCM1608-0603") (pin "1") (pinfunction "P$1_1") (pintype "bidirectional"))
      (node (ref "HALL1") (pin "1") (pinfunction "S_1") (pintype "passive"))
      (node (ref "HALL2") (pin "1") (pinfunction "S_1") (pintype "passive"))
      (node (ref "IC1") (pin "2") (pinfunction "VOUT_2") (pintype "power_in"))
      (node (ref "IMU_DROTEK") (pin "3") (pinfunction "S_3") (pintype "passive"))
      (node (ref "I_T_V") (pin "4") (pinfunction "S_4") (pintype "passive"))
      (node (ref "NL-652ETTL") (pin "1") (pinfunction "S_1") (pintype "passive"))
      (node (ref "NRF24L01+") (pin "2") (pinfunction "2_2") (pintype "passive"))
      (node (ref "R11") (pin "2") (pinfunction "2_2") (pintype "passive"))
      (node (ref "R17") (pin "1") (pinfunction "1_1") (pintype "passive"))
      (node (ref "R18") (pin "1") (pinfunction "1_1") (pintype "passive"))
      (node (ref "R20") (pin "2") (pinfunction "2_2") (pintype "passive"))
      (node (ref "R22") (pin "1") (pinfunction "1_1") (pintype "passive"))
      (node (ref "R23") (pin "1") (pinfunction "1_1") (pintype "passive"))
      (node (ref "R3") (pin "1") (pinfunction "1_1") (pintype "passive"))
      (node (ref "R9") (pin "1") (pinfunction "1_1") (pintype "passive"))
      (node (ref "SWD") (pin "1") (pinfunction "S_1") (pintype "passive"))
      (node (ref "U$3") (pin "5") (pinfunction "VCC_5") (pintype "bidirectional"))
      (node (ref "U1") (pin "1") (pinfunction "VBAT_1") (pintype "power_in"))
      (node (ref "U1") (pin "19") (pinfunction "VDD_4_19") (pintype "power_in"))
      (node (ref "U1") (pin "32") (pinfunction "VDD_1_32") (pintype "power_in"))
      (node (ref "U1") (pin "48") (pinfunction "VDD_2_48") (pintype "power_in"))
      (node (ref "U1") (pin "64") (pinfunction "VDD_3_64") (pintype "power_in"))
      (node (ref "X1") (pin "2") (pinfunction "S_2") (pintype "passive"))
      (node (ref "X1") (pin "4") (pinfunction "S_4") (pintype "passive"))
    )
    (net (code "78") (name "unconnected-(IMU_DROTEKB-S-Pad2)") (class "Default")
      (node (ref "IMU_DROTEK") (pin "2") (pinfunction "S_2") (pintype "passive"))
    )
    (net (code "79") (name "unconnected-(U$3-GPIO2-Pad8)") (class "Default")
      (node (ref "U$3") (pin "8") (pinfunction "GPIO2_8") (pintype "bidirectional"))
    )
    (net (code "80") (name "unconnected-(U1B-PA15-Pad50)") (class "Default")
      (node (ref "U1") (pin "50") (pinfunction "PA15_50") (pintype "bidirectional"))
    )
    (net (code "81") (name "unconnected-(U1E-PB0-Pad26)") (class "Default")
      (node (ref "U1") (pin "26") (pinfunction "PB0_26") (pintype "bidirectional"))
    )
    (net (code "82") (name "unconnected-(U1E-PB1-Pad27)") (class "Default")
      (node (ref "U1") (pin "27") (pinfunction "PB1_27") (pintype "bidirectional"))
    )
    (net (code "83") (name "unconnected-(U1E-PB4-Pad56)") (class "Default")
      (node (ref "U1") (pin "56") (pinfunction "PB4_56") (pintype "bidirectional"))
    )
    (net (code "84") (name "unconnected-(U1E-PB5-Pad57)") (class "Default")
      (node (ref "U1") (pin "57") (pinfunction "PB5_57") (pintype "bidirectional"))
    )
    (net (code "85") (name "unconnected-(U1F-PC13-Pad2)") (class "Default")
      (node (ref "U1") (pin "2") (pinfunction "PC13_2") (pintype "bidirectional"))
    )
    (net (code "86") (name "unconnected-(U1F-PC14-Pad3)") (class "Default")
      (node (ref "U1") (pin "3") (pinfunction "PC14_3") (pintype "bidirectional"))
    )
    (net (code "87") (name "unconnected-(U1F-PC15-Pad4)") (class "Default")
      (node (ref "U1") (pin "4") (pinfunction "PC15_4") (pintype "bidirectional"))
    )
    (net (code "88") (name "unconnected-(U1H-PD2-Pad54)") (class "Default")
      (node (ref "U1") (pin "54") (pinfunction "PD2_54") (pintype "bidirectional"))
    )
  )
)
